# amc7135-by-12-16mm-led-aux-driver-mk-1_0.net
KiCad netlist of a schematic drawn in EAGLE
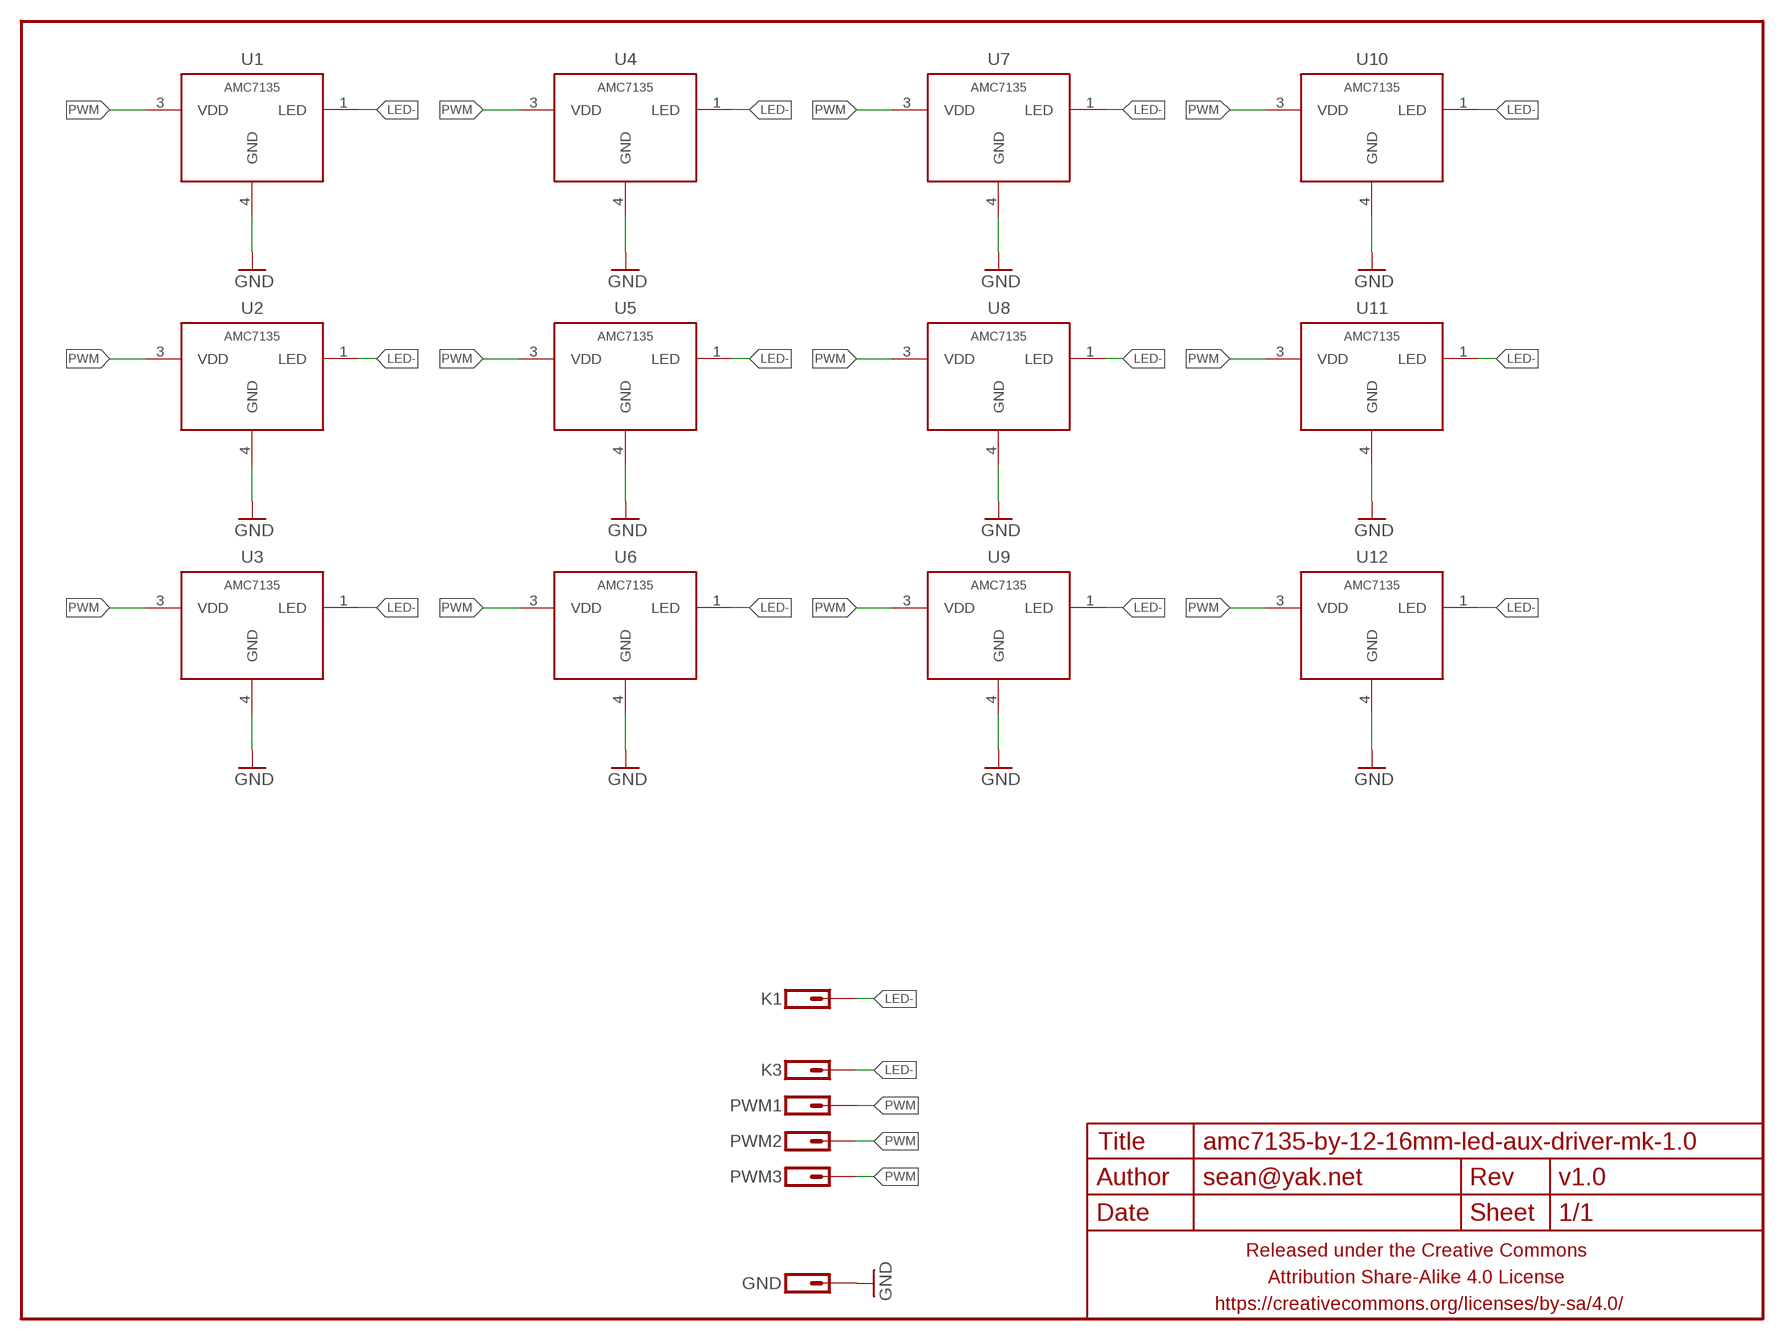
[diagram p0: schematic, sheet 1]

(export (version "E")
  (design (tool "Eeschema 10.0.6"))
  (components
    (comp (ref "FRAME1")
      (value "FRAME-LETTERNO_PACKAGE")
      (footprint "eagle-import:DUMMY")
      (fields (field (name "DESIGNER") "sean@yak.net") (field (name "VERSION") "v1.0"))
      (libsource (lib "eagle-import") (part "FRAME-LETTERNO_PACKAGE"))
    )
    (comp (ref "GND")
      (value "M01SMD-1MM-DIA-NS")
      (footprint "eagle-import:1X01-SMD-1MM-DIA-NS")
      (libsource (lib "eagle-import") (part "M01SMD-1MM-DIA-NS"))
    )
    (comp (ref "K1")
      (value "M011X01-0.9MM-CIR")
      (footprint "eagle-import:1X01-0.9MM-CIR")
      (libsource (lib "eagle-import") (part "M011X01-0.9MM-CIR"))
    )
    (comp (ref "K3")
      (value "M01SMD-1MM-DIA-NS")
      (footprint "eagle-import:1X01-SMD-1MM-DIA-NS")
      (libsource (lib "eagle-import") (part "M01SMD-1MM-DIA-NS"))
    )
    (comp (ref "PWM1")
      (value "M01PTH-0.7MM")
      (footprint "eagle-import:1X01-0.7MM")
      (libsource (lib "eagle-import") (part "M01PTH-0.7MM"))
    )
    (comp (ref "PWM2")
      (value "M01PTH-0.7MM")
      (footprint "eagle-import:1X01-0.7MM")
      (libsource (lib "eagle-import") (part "M01PTH-0.7MM"))
    )
    (comp (ref "PWM3")
      (value "M01SMD-1MM-DIA-NS")
      (footprint "eagle-import:1X01-SMD-1MM-DIA-NS")
      (libsource (lib "eagle-import") (part "M01SMD-1MM-DIA-NS"))
    )
    (comp (ref "U1")
      (value "AMC7135")
      (footprint "eagle-import:SOT89-NOTHERM-ROUNDED-LESS")
      (libsource (lib "eagle-import") (part "AMC7135SOT-89-NOTHERM-ROUNDED-LESS"))
    )
    (comp (ref "U2")
      (value "AMC7135")
      (footprint "eagle-import:SOT89-NOTHERM-ROUNDED-LESS")
      (libsource (lib "eagle-import") (part "AMC7135SOT-89-NOTHERM-ROUNDED-LESS"))
    )
    (comp (ref "U3")
      (value "AMC7135")
      (footprint "eagle-import:SOT89-NOTHERM-ROUNDED-LESS")
      (libsource (lib "eagle-import") (part "AMC7135SOT-89-NOTHERM-ROUNDED-LESS"))
    )
    (comp (ref "U4")
      (value "AMC7135")
      (footprint "eagle-import:SOT89-NOTHERM-ROUNDED-LESS")
      (libsource (lib "eagle-import") (part "AMC7135SOT-89-NOTHERM-ROUNDED-LESS"))
    )
    (comp (ref "U5")
      (value "AMC7135")
      (footprint "eagle-import:SOT89-NOTHERM-ROUNDED-LESS")
      (libsource (lib "eagle-import") (part "AMC7135SOT-89-NOTHERM-ROUNDED-LESS"))
    )
    (comp (ref "U6")
      (value "AMC7135")
      (footprint "eagle-import:SOT89-NOTHERM-ROUNDED-LESS")
      (libsource (lib "eagle-import") (part "AMC7135SOT-89-NOTHERM-ROUNDED-LESS"))
    )
    (comp (ref "U7")
      (value "AMC7135")
      (footprint "eagle-import:SOT89-NOTHERM-ROUNDED-LESS")
      (libsource (lib "eagle-import") (part "AMC7135SOT-89-NOTHERM-ROUNDED-LESS"))
    )
    (comp (ref "U8")
      (value "AMC7135")
      (footprint "eagle-import:SOT89-NOTHERM-ROUNDED-LESS")
      (libsource (lib "eagle-import") (part "AMC7135SOT-89-NOTHERM-ROUNDED-LESS"))
    )
    (comp (ref "U9")
      (value "AMC7135")
      (footprint "eagle-import:SOT89-NOTHERM-ROUNDED-LESS")
      (libsource (lib "eagle-import") (part "AMC7135SOT-89-NOTHERM-ROUNDED-LESS"))
    )
    (comp (ref "U10")
      (value "AMC7135")
      (footprint "eagle-import:SOT89-NOTHERM-ROUNDED-LESS")
      (libsource (lib "eagle-import") (part "AMC7135SOT-89-NOTHERM-ROUNDED-LESS"))
    )
    (comp (ref "U11")
      (value "AMC7135")
      (footprint "eagle-import:SOT89-NOTHERM-ROUNDED-LESS")
      (libsource (lib "eagle-import") (part "AMC7135SOT-89-NOTHERM-ROUNDED-LESS"))
    )
    (comp (ref "U12")
      (value "AMC7135")
      (footprint "eagle-import:SOT89-NOTHERM-ROUNDED-LESS")
      (libsource (lib "eagle-import") (part "AMC7135SOT-89-NOTHERM-ROUNDED-LESS"))
    )
  )
  (nets
    (net (code "1") (name "GND") (class "Default")
      (node (ref "GND") (pin "P$1") (pinfunction "1_P$1") (pintype "passive"))
      (node (ref "U1") (pin "4") (pinfunction "GND_4") (pintype "bidirectional"))
      (node (ref "U10") (pin "4") (pinfunction "GND_4") (pintype "bidirectional"))
      (node (ref "U11") (pin "4") (pinfunction "GND_4") (pintype "bidirectional"))
      (node (ref "U12") (pin "4") (pinfunction "GND_4") (pintype "bidirectional"))
      (node (ref "U2") (pin "4") (pinfunction "GND_4") (pintype "bidirectional"))
      (node (ref "U3") (pin "4") (pinfunction "GND_4") (pintype "bidirectional"))
      (node (ref "U4") (pin "4") (pinfunction "GND_4") (pintype "bidirectional"))
      (node (ref "U5") (pin "4") (pinfunction "GND_4") (pintype "bidirectional"))
      (node (ref "U6") (pin "4") (pinfunction "GND_4") (pintype "bidirectional"))
      (node (ref "U7") (pin "4") (pinfunction "GND_4") (pintype "bidirectional"))
      (node (ref "U8") (pin "4") (pinfunction "GND_4") (pintype "bidirectional"))
      (node (ref "U9") (pin "4") (pinfunction "GND_4") (pintype "bidirectional"))
    )
    (net (code "2") (name "LED-") (class "Default")
      (node (ref "K1") (pin "P$1") (pinfunction "1_P$1") (pintype "passive"))
      (node (ref "K3") (pin "P$1") (pinfunction "1_P$1") (pintype "passive"))
      (node (ref "U1") (pin "1") (pinfunction "LED_1") (pintype "bidirectional"))
      (node (ref "U10") (pin "1") (pinfunction "LED_1") (pintype "bidirectional"))
      (node (ref "U11") (pin "1") (pinfunction "LED_1") (pintype "bidirectional"))
      (node (ref "U12") (pin "1") (pinfunction "LED_1") (pintype "bidirectional"))
      (node (ref "U2") (pin "1") (pinfunction "LED_1") (pintype "bidirectional"))
      (node (ref "U3") (pin "1") (pinfunction "LED_1") (pintype "bidirectional"))
      (node (ref "U4") (pin "1") (pinfunction "LED_1") (pintype "bidirectional"))
      (node (ref "U5") (pin "1") (pinfunction "LED_1") (pintype "bidirectional"))
      (node (ref "U6") (pin "1") (pinfunction "LED_1") (pintype "bidirectional"))
      (node (ref "U7") (pin "1") (pinfunction "LED_1") (pintype "bidirectional"))
      (node (ref "U8") (pin "1") (pinfunction "LED_1") (pintype "bidirectional"))
      (node (ref "U9") (pin "1") (pinfunction "LED_1") (pintype "bidirectional"))
    )
    (net (code "3") (name "PWM") (class "Default")
      (node (ref "PWM1") (pin "1") (pinfunction "1_1") (pintype "passive"))
      (node (ref "PWM2") (pin "1") (pinfunction "1_1") (pintype "passive"))
      (node (ref "PWM3") (pin "P$1") (pinfunction "1_P$1") (pintype "passive"))
      (node (ref "U1") (pin "3") (pinfunction "VDD_3") (pintype "bidirectional"))
      (node (ref "U10") (pin "3") (pinfunction "VDD_3") (pintype "bidirectional"))
      (node (ref "U11") (pin "3") (pinfunction "VDD_3") (pintype "bidirectional"))
      (node (ref "U12") (pin "3") (pinfunction "VDD_3") (pintype "bidirectional"))
      (node (ref "U2") (pin "3") (pinfunction "VDD_3") (pintype "bidirectional"))
      (node (ref "U3") (pin "3") (pinfunction "VDD_3") (pintype "bidirectional"))
      (node (ref "U4") (pin "3") (pinfunction "VDD_3") (pintype "bidirectional"))
      (node (ref "U5") (pin "3") (pinfunction "VDD_3") (pintype "bidirectional"))
      (node (ref "U6") (pin "3") (pinfunction "VDD_3") (pintype "bidirectional"))
      (node (ref "U7") (pin "3") (pinfunction "VDD_3") (pintype "bidirectional"))
      (node (ref "U8") (pin "3") (pinfunction "VDD_3") (pintype "bidirectional"))
      (node (ref "U9") (pin "3") (pinfunction "VDD_3") (pintype "bidirectional"))
    )
  )
)
